# UKU100rs.net
KiCad netlist of a schematic drawn in Altium Designer
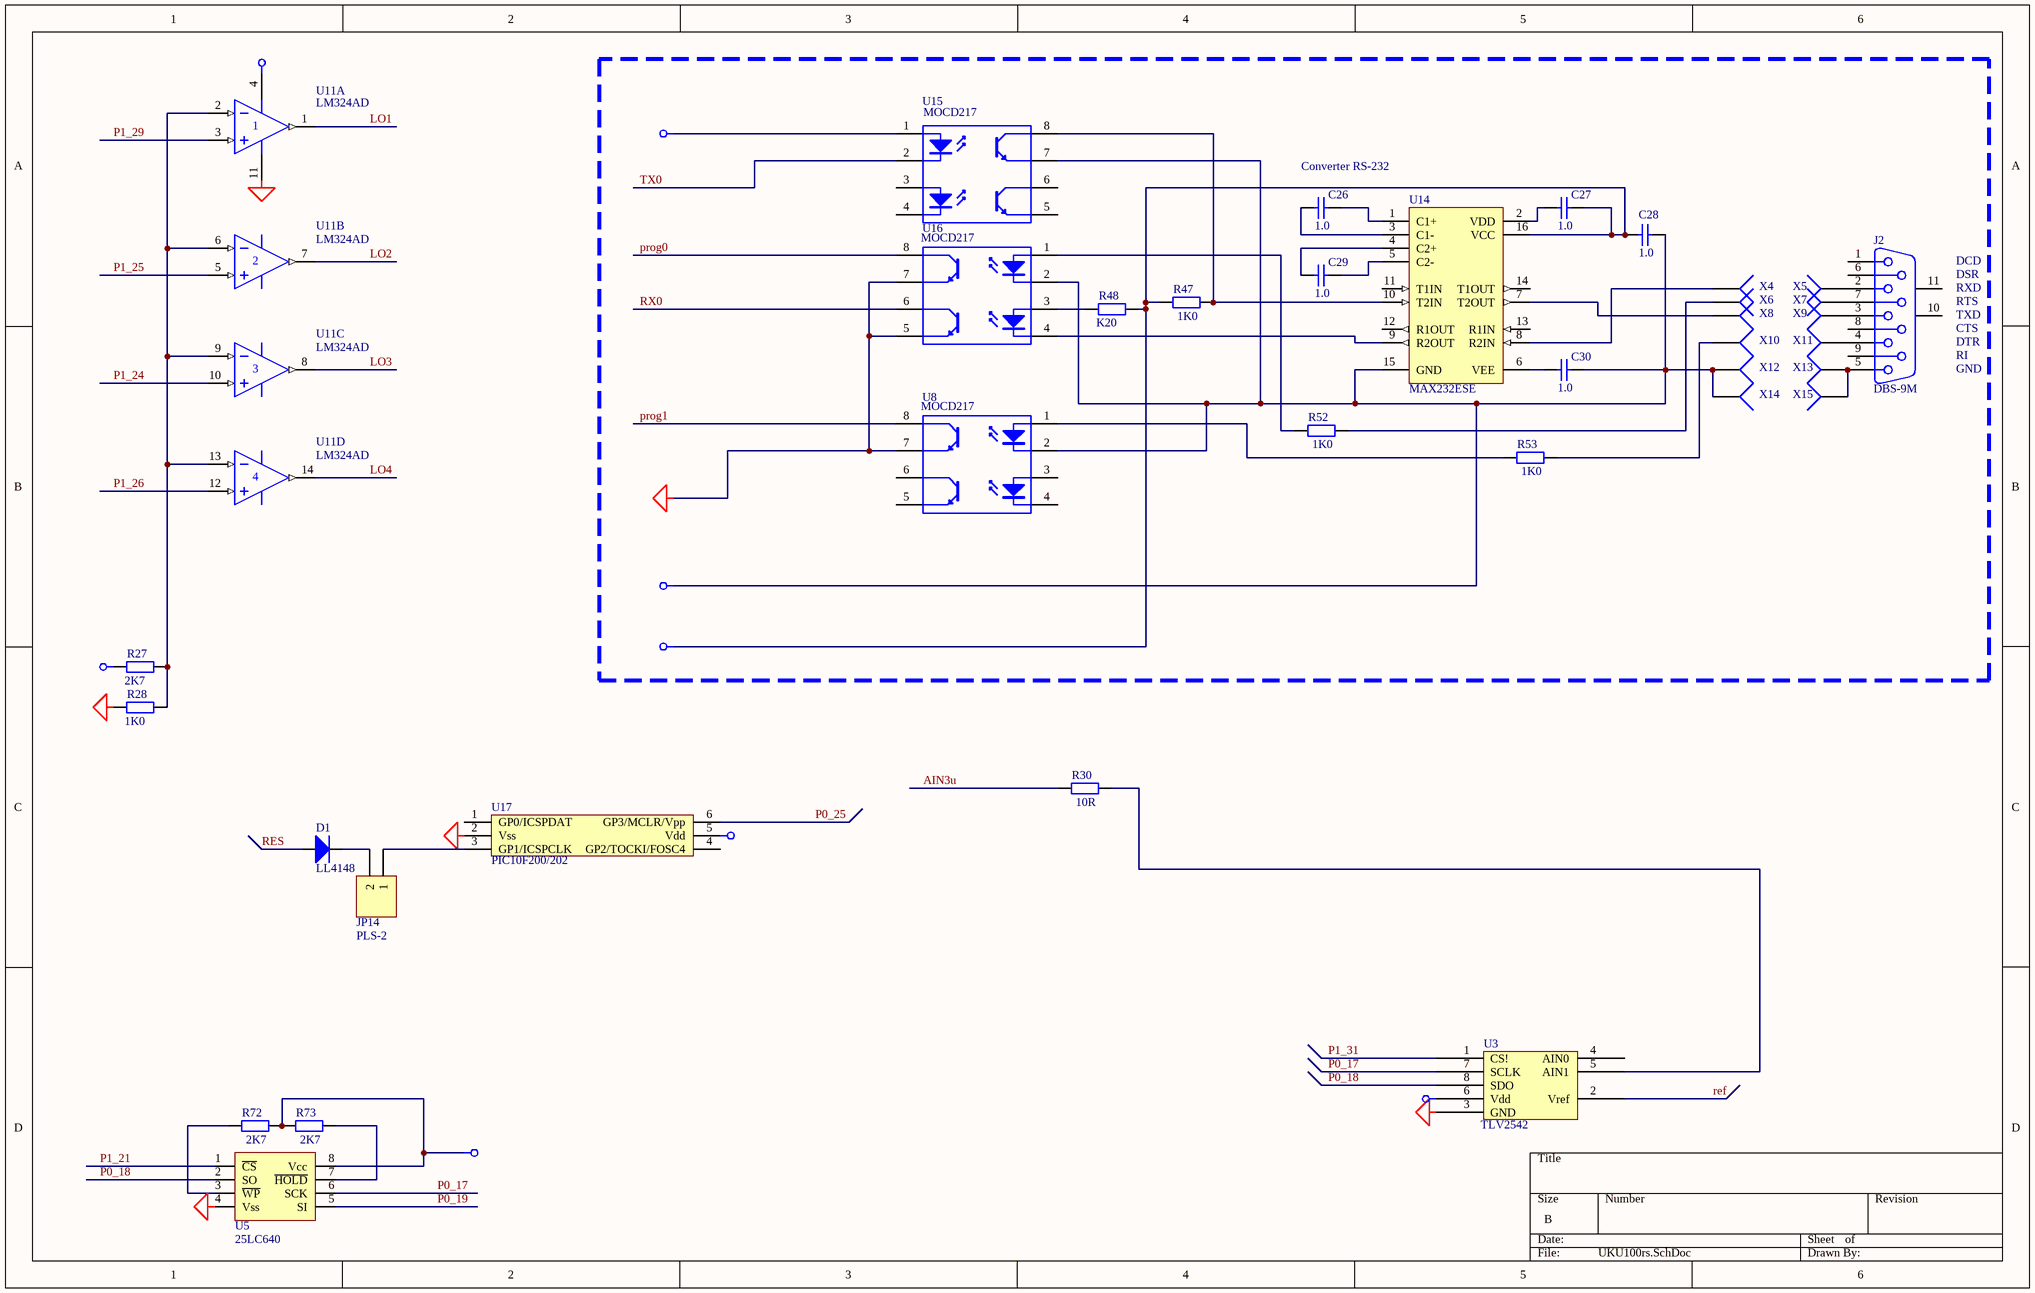
[diagram p0: UKU100rs.SchDoc]

(export (version "E")
  (design (tool "Eeschema 10.0.6"))
  (components
    (comp (ref "C26")
      (value "1.0")
      (footprint "C3216-1206")
      (description "Capacitor (Semiconductor SIM Model)")
      (fields (field (name "MANUFACTURER") "Generic Components") (field (name "PUBLISHER") "Altium Limited"))
      (libsource (lib "Miscellaneous Devices") (part "Cap Semi"))
    )
    (comp (ref "C27")
      (value "1.0")
      (footprint "_1206")
      (description "Capacitor (Semiconductor SIM Model)")
      (fields (field (name "MANUFACTURER") "Generic Components") (field (name "PUBLISHER") "Altium Limited"))
      (libsource (lib "Miscellaneous Devices") (part "Cap Semi"))
    )
    (comp (ref "C28")
      (value "1.0")
      (footprint "C3216-1206")
      (description "Capacitor (Semiconductor SIM Model)")
      (fields (field (name "MANUFACTURER") "Generic Components") (field (name "PUBLISHER") "Altium Limited"))
      (libsource (lib "Miscellaneous Devices") (part "Cap Semi"))
    )
    (comp (ref "C29")
      (value "1.0")
      (footprint "C3216-1206")
      (description "Capacitor (Semiconductor SIM Model)")
      (fields (field (name "MANUFACTURER") "Generic Components") (field (name "PUBLISHER") "Altium Limited"))
      (libsource (lib "Miscellaneous Devices") (part "Cap Semi"))
    )
    (comp (ref "C30")
      (value "1.0")
      (footprint "C3216-1206")
      (description "Capacitor (Semiconductor SIM Model)")
      (fields (field (name "MANUFACTURER") "Generic Components") (field (name "PUBLISHER") "Altium Limited"))
      (libsource (lib "Miscellaneous Devices") (part "Cap Semi"))
    )
    (comp (ref "D1")
      (value "LL4148")
      (footprint "_1206D")
      (description "Default Diode")
      (fields (field (name "MANUFACTURER") "Generic Components") (field (name "PUBLISHER") "Altium Limited"))
      (libsource (lib "Pal") (part "Diode"))
    )
    (comp (ref "J2")
      (value "DBS-9M")
      (footprint "DSUB_N9")
      (description "Receptacle Assembly, 9 Position, Right Angle")
      (fields (field (name "MANUFACTURER") "Generic Components") (field (name "PUBLISHER") "Altium Limited"))
      (libsource (lib "Miscellaneous Connectors") (part "D Connector 9"))
    )
    (comp (ref "JP14")
      (value "PLS-2")
      (footprint "HDR1X2")
      (description "Header, 2-Pin")
      (fields (field (name "MANUFACTURER") "Generic Components") (field (name "PUBLISHER") "Altium Limited"))
      (libsource (lib "Miscellaneous Connectors") (part "Header 2"))
    )
    (comp (ref "R27")
      (value "2K7")
      (footprint "_1206")
      (description "Resistor")
      (fields (field (name "MANUFACTURER") "Generic Components") (field (name "PUBLISHER") "Altium Limited"))
      (libsource (lib "Miscellaneous Devices") (part "Res2"))
    )
    (comp (ref "R28")
      (value "1K0")
      (footprint "_1206")
      (description "Resistor")
      (fields (field (name "MANUFACTURER") "Generic Components") (field (name "PUBLISHER") "Altium Limited"))
      (libsource (lib "Miscellaneous Devices") (part "Res2"))
    )
    (comp (ref "R30")
      (value "10R")
      (footprint "_1206")
      (description "Resistor")
      (fields (field (name "MANUFACTURER") "Generic Components") (field (name "PUBLISHER") "Altium Limited"))
      (libsource (lib "Miscellaneous Devices") (part "Res2"))
    )
    (comp (ref "R47")
      (value "1K0")
      (footprint "_1206")
      (description "Resistor")
      (fields (field (name "MANUFACTURER") "Generic Components") (field (name "PUBLISHER") "Altium Limited"))
      (libsource (lib "Miscellaneous Devices") (part "Res2"))
    )
    (comp (ref "R48")
      (value "K20")
      (footprint "_1206")
      (description "Resistor")
      (fields (field (name "MANUFACTURER") "Generic Components") (field (name "PUBLISHER") "Altium Limited"))
      (libsource (lib "Miscellaneous Devices") (part "Res2"))
    )
    (comp (ref "R52")
      (value "1K0")
      (footprint "_1206")
      (description "Resistor")
      (fields (field (name "MANUFACTURER") "Generic Components") (field (name "PUBLISHER") "Altium Limited"))
      (libsource (lib "Miscellaneous Devices") (part "Res2"))
    )
    (comp (ref "R53")
      (value "1K0")
      (footprint "_1206")
      (description "Resistor")
      (fields (field (name "MANUFACTURER") "Generic Components") (field (name "PUBLISHER") "Altium Limited"))
      (libsource (lib "Miscellaneous Devices") (part "Res2"))
    )
    (comp (ref "R72")
      (value "2K7")
      (footprint "_1206")
      (description "Resistor")
      (fields (field (name "MANUFACTURER") "Generic Components") (field (name "PUBLISHER") "Altium Limited"))
      (libsource (lib "Miscellaneous Devices") (part "Res2"))
    )
    (comp (ref "R73")
      (value "2K7")
      (footprint "_1206")
      (description "Resistor")
      (fields (field (name "MANUFACTURER") "Generic Components") (field (name "PUBLISHER") "Altium Limited"))
      (libsource (lib "Miscellaneous Devices") (part "Res2"))
    )
    (comp (ref "U3") (value "TLV2542") (footprint "SO-G8") (libsource (lib "MNS_A") (part "TLV2542")))
    (comp (ref "U5") (value "25LC640") (footprint "SO-G8/D5") (libsource (lib "PAL") (part "25LC640")))
    (comp (ref "U8") (value "MOCD217") (footprint "SO-G8") (libsource (lib "PAL") (part "MOCD217")))
    (comp (ref "U11")
      (value "LM324AD")
      (footprint "SO-G14/G3.3")
      (description "Quadruple Operational Amplifier")
      (fields (field (name "MANUFACTURER") "Texas Instruments") (field (name "PUBLISHER") "Altium Limited"))
      (libsource (lib "TI Operational Amplifier") (part "LM324AD"))
    )
    (comp (ref "U14")
      (value "MAX232ESE")
      (footprint "SO-G16")
      (description "+5V Powered, Multi-Channel RS-232 Driver/Receiver")
      (fields (field (name "MANUFACTURER") "Maxim") (field (name "PUBLISHER") "Altium Limited"))
      (libsource (lib "Maxim Communication Transceiver") (part "MAX232ESE"))
    )
    (comp (ref "U15") (value "MOCD217") (footprint "SO-G8") (libsource (lib "PAL") (part "MOCD217")))
    (comp (ref "U16") (value "MOCD217") (footprint "SO-G8") (libsource (lib "PAL") (part "MOCD217")))
    (comp (ref "U17")
      (value "PIC10F200/202")
      (footprint "SOT23 - 6")
      (libsource (lib "PAL") (part "PIC10F200/202"))
    )
    (comp (ref "X4")
      (value "~")
      (footprint "PIN1")
      (description "Socket")
      (fields (field (name "MANUFACTURER") "Generic Components") (field (name "PUBLISHER") "Altium Limited"))
      (libsource (lib "Miscellaneous Connectors") (part "Socket"))
    )
    (comp (ref "X5")
      (value "~")
      (footprint "PIN1")
      (description "Socket")
      (fields (field (name "MANUFACTURER") "Generic Components") (field (name "PUBLISHER") "Altium Limited"))
      (libsource (lib "Miscellaneous Connectors") (part "Socket"))
    )
    (comp (ref "X6")
      (value "~")
      (footprint "PIN1")
      (description "Socket")
      (fields (field (name "MANUFACTURER") "Generic Components") (field (name "PUBLISHER") "Altium Limited"))
      (libsource (lib "Miscellaneous Connectors") (part "Socket"))
    )
    (comp (ref "X7")
      (value "~")
      (footprint "PIN1")
      (description "Socket")
      (fields (field (name "MANUFACTURER") "Generic Components") (field (name "PUBLISHER") "Altium Limited"))
      (libsource (lib "Miscellaneous Connectors") (part "Socket"))
    )
    (comp (ref "X8")
      (value "~")
      (footprint "PIN1")
      (description "Socket")
      (fields (field (name "MANUFACTURER") "Generic Components") (field (name "PUBLISHER") "Altium Limited"))
      (libsource (lib "Miscellaneous Connectors") (part "Socket"))
    )
    (comp (ref "X9")
      (value "~")
      (footprint "PIN1")
      (description "Socket")
      (fields (field (name "MANUFACTURER") "Generic Components") (field (name "PUBLISHER") "Altium Limited"))
      (libsource (lib "Miscellaneous Connectors") (part "Socket"))
    )
    (comp (ref "X10")
      (value "~")
      (footprint "PIN1")
      (description "Socket")
      (fields (field (name "MANUFACTURER") "Generic Components") (field (name "PUBLISHER") "Altium Limited"))
      (libsource (lib "Miscellaneous Connectors") (part "Socket"))
    )
    (comp (ref "X11")
      (value "~")
      (footprint "PIN1")
      (description "Socket")
      (fields (field (name "MANUFACTURER") "Generic Components") (field (name "PUBLISHER") "Altium Limited"))
      (libsource (lib "Miscellaneous Connectors") (part "Socket"))
    )
    (comp (ref "X12")
      (value "~")
      (footprint "PIN1")
      (description "Socket")
      (fields (field (name "MANUFACTURER") "Generic Components") (field (name "PUBLISHER") "Altium Limited"))
      (libsource (lib "Miscellaneous Connectors") (part "Socket"))
    )
    (comp (ref "X13")
      (value "~")
      (footprint "PIN1")
      (description "Socket")
      (fields (field (name "MANUFACTURER") "Generic Components") (field (name "PUBLISHER") "Altium Limited"))
      (libsource (lib "Miscellaneous Connectors") (part "Socket"))
    )
    (comp (ref "X14")
      (value "~")
      (footprint "PIN1")
      (description "Socket")
      (fields (field (name "MANUFACTURER") "Generic Components") (field (name "PUBLISHER") "Altium Limited"))
      (libsource (lib "Miscellaneous Connectors") (part "Socket"))
    )
    (comp (ref "X15")
      (value "~")
      (footprint "PIN1")
      (description "Socket")
      (fields (field (name "MANUFACTURER") "Generic Components") (field (name "PUBLISHER") "Altium Limited"))
      (libsource (lib "Miscellaneous Connectors") (part "Socket"))
    )
  )
  (nets
    (net (code "1") (name "+3v3") (class "Default")
      (node (ref "U17") (pin "5") (pinfunction "Vdd_5") (pintype "passive"))
    )
    (net (code "2") (name "+3v3_") (class "Default")
      (node (ref "U15") (pin "1") (pinfunction "A_1") (pintype "passive"))
    )
    (net (code "3") (name "+5v") (class "Default")
      (node (ref "R27") (pin "1") (pinfunction "1_1") (pintype "passive"))
      (node (ref "R72") (pin "2") (pinfunction "2_2") (pintype "passive"))
      (node (ref "R73") (pin "1") (pinfunction "1_1") (pintype "passive"))
      (node (ref "U11") (pin "4") (pinfunction "V+_4") (pintype "power_in"))
      (node (ref "U3") (pin "6") (pinfunction "Vdd_6") (pintype "passive"))
      (node (ref "U5") (pin "8") (pinfunction "Vcc_8") (pintype "passive"))
    )
    (net (code "4") (name "+5v_iz") (class "Default")
      (node (ref "C27") (pin "2") (pinfunction "2_2") (pintype "passive"))
      (node (ref "C28") (pin "1") (pinfunction "1_1") (pintype "passive"))
      (node (ref "R47") (pin "1") (pinfunction "1_1") (pintype "passive"))
      (node (ref "R48") (pin "2") (pinfunction "2_2") (pintype "passive"))
      (node (ref "U14") (pin "16") (pinfunction "VCC_16") (pintype "power_in"))
    )
    (net (code "5") (name "-5v_iz") (class "Default")
      (node (ref "C28") (pin "2") (pinfunction "2_2") (pintype "passive"))
      (node (ref "C30") (pin "2") (pinfunction "2_2") (pintype "passive"))
      (node (ref "U14") (pin "15") (pinfunction "GND_15") (pintype "power_in"))
      (node (ref "U15") (pin "7") (pinfunction "E_7") (pintype "passive"))
      (node (ref "U16") (pin "2") (pinfunction "K_2") (pintype "passive"))
      (node (ref "U8") (pin "2") (pinfunction "K_2") (pintype "passive"))
      (node (ref "X12") (pin "1") (pinfunction "1_1") (pintype "passive"))
      (node (ref "X14") (pin "1") (pinfunction "1_1") (pintype "passive"))
    )
    (net (code "6") (name "/AIN3u") (class "Default")
      (node (ref "R30") (pin "1") (pinfunction "1_1") (pintype "passive"))
    )
    (net (code "7") (name "/LO1") (class "Default")
      (node (ref "U11") (pin "1") (pinfunction "OUT_1") (pintype "output"))
    )
    (net (code "8") (name "/LO2") (class "Default")
      (node (ref "U11") (pin "7") (pinfunction "OUT_7") (pintype "output"))
    )
    (net (code "9") (name "/LO3") (class "Default")
      (node (ref "U11") (pin "8") (pinfunction "OUT_8") (pintype "output"))
    )
    (net (code "10") (name "/LO4") (class "Default")
      (node (ref "U11") (pin "14") (pinfunction "OUT_14") (pintype "output"))
    )
    (net (code "11") (name "/P0_17") (class "Default")
      (node (ref "U3") (pin "7") (pinfunction "SCLK_7") (pintype "passive"))
      (node (ref "U5") (pin "6") (pinfunction "SCK_6") (pintype "passive"))
    )
    (net (code "12") (name "/P0_18") (class "Default")
      (node (ref "U3") (pin "8") (pinfunction "SDO_8") (pintype "passive"))
      (node (ref "U5") (pin "2") (pinfunction "SO_2") (pintype "passive"))
    )
    (net (code "13") (name "/P0_19") (class "Default")
      (node (ref "U5") (pin "5") (pinfunction "SI_5") (pintype "passive"))
    )
    (net (code "14") (name "/P0_25") (class "Default")
      (node (ref "U17") (pin "6") (pinfunction "GP3/MCLR/Vpp_6") (pintype "passive"))
    )
    (net (code "15") (name "/P1_21") (class "Default")
      (node (ref "U5") (pin "1") (pinfunction "~{CS}_1") (pintype "passive"))
    )
    (net (code "16") (name "/P1_24") (class "Default")
      (node (ref "U11") (pin "10") (pinfunction "IN+_10") (pintype "input"))
    )
    (net (code "17") (name "/P1_25") (class "Default")
      (node (ref "U11") (pin "5") (pinfunction "IN+_5") (pintype "input"))
    )
    (net (code "18") (name "/P1_26") (class "Default")
      (node (ref "U11") (pin "12") (pinfunction "IN+_12") (pintype "input"))
    )
    (net (code "19") (name "/P1_29") (class "Default")
      (node (ref "U11") (pin "3") (pinfunction "IN+_3") (pintype "input"))
    )
    (net (code "20") (name "/P1_31") (class "Default")
      (node (ref "U3") (pin "1") (pinfunction "CS!_1") (pintype "passive"))
    )
    (net (code "21") (name "/RES") (class "Default")
      (node (ref "D1") (pin "1") (pinfunction "A_1") (pintype "passive"))
    )
    (net (code "22") (name "/RX0") (class "Default")
      (node (ref "U16") (pin "6") (pinfunction "C_6") (pintype "passive"))
    )
    (net (code "23") (name "/TX0") (class "Default")
      (node (ref "U15") (pin "2") (pinfunction "K_2") (pintype "passive"))
    )
    (net (code "24") (name "/prog0") (class "Default")
      (node (ref "U16") (pin "8") (pinfunction "C_8") (pintype "passive"))
    )
    (net (code "25") (name "/prog1") (class "Default")
      (node (ref "U8") (pin "8") (pinfunction "C_8") (pintype "passive"))
    )
    (net (code "26") (name "/ref") (class "Default")
      (node (ref "U3") (pin "2") (pinfunction "Vref_2") (pintype "passive"))
    )
    (net (code "27") (name "GND") (class "Default")
      (node (ref "R28") (pin "1") (pinfunction "1_1") (pintype "passive"))
      (node (ref "U11") (pin "11") (pinfunction "V-_11") (pintype "power_in"))
      (node (ref "U16") (pin "5") (pinfunction "E_5") (pintype "passive"))
      (node (ref "U16") (pin "7") (pinfunction "E_7") (pintype "passive"))
      (node (ref "U17") (pin "2") (pinfunction "Vss_2") (pintype "passive"))
      (node (ref "U3") (pin "3") (pinfunction "GND_3") (pintype "passive"))
      (node (ref "U5") (pin "4") (pinfunction "Vss_4") (pintype "passive"))
      (node (ref "U8") (pin "7") (pinfunction "E_7") (pintype "passive"))
    )
    (net (code "28") (name "Net-(D1-K)") (class "Default")
      (node (ref "D1") (pin "2") (pinfunction "K_2") (pintype "passive"))
      (node (ref "JP14") (pin "2") (pinfunction "2_2") (pintype "passive"))
    )
    (net (code "29") (name "Net-(J2-Pad2)") (class "Default")
      (node (ref "J2") (pin "2") (pinfunction "2_2") (pintype "passive"))
      (node (ref "X5") (pin "1") (pinfunction "1_1") (pintype "passive"))
    )
    (net (code "30") (name "Net-(J2-Pad3)") (class "Default")
      (node (ref "J2") (pin "3") (pinfunction "3_3") (pintype "passive"))
      (node (ref "X9") (pin "1") (pinfunction "1_1") (pintype "passive"))
    )
    (net (code "31") (name "Net-(J2-Pad4)") (class "Default")
      (node (ref "J2") (pin "4") (pinfunction "4_4") (pintype "passive"))
      (node (ref "X11") (pin "1") (pinfunction "1_1") (pintype "passive"))
    )
    (net (code "32") (name "Net-(J2-Pad5)") (class "Default")
      (node (ref "J2") (pin "5") (pinfunction "5_5") (pintype "passive"))
      (node (ref "X13") (pin "1") (pinfunction "1_1") (pintype "passive"))
      (node (ref "X15") (pin "1") (pinfunction "1_1") (pintype "passive"))
    )
    (net (code "33") (name "Net-(J2-Pad7)") (class "Default")
      (node (ref "J2") (pin "7") (pinfunction "7_7") (pintype "passive"))
      (node (ref "X7") (pin "1") (pinfunction "1_1") (pintype "passive"))
    )
    (net (code "34") (name "Net-(R48-Pad1)") (class "Default")
      (node (ref "R48") (pin "1") (pinfunction "1_1") (pintype "passive"))
      (node (ref "U16") (pin "3") (pinfunction "A_3") (pintype "passive"))
    )
    (net (code "35") (name "Net-(R52-Pad1)") (class "Default")
      (node (ref "R52") (pin "1") (pinfunction "1_1") (pintype "passive"))
      (node (ref "U16") (pin "1") (pinfunction "A_1") (pintype "passive"))
    )
    (net (code "36") (name "Net-(R52-Pad2)") (class "Default")
      (node (ref "R52") (pin "2") (pinfunction "2_2") (pintype "passive"))
      (node (ref "X6") (pin "1") (pinfunction "1_1") (pintype "passive"))
    )
    (net (code "37") (name "Net-(R53-Pad1)") (class "Default")
      (node (ref "R53") (pin "1") (pinfunction "1_1") (pintype "passive"))
      (node (ref "U8") (pin "1") (pinfunction "A_1") (pintype "passive"))
    )
    (net (code "38") (name "Net-(R53-Pad2)") (class "Default")
      (node (ref "R53") (pin "2") (pinfunction "2_2") (pintype "passive"))
      (node (ref "X10") (pin "1") (pinfunction "1_1") (pintype "passive"))
    )
    (net (code "39") (name "Net-(U3-AIN1)") (class "Default")
      (node (ref "R30") (pin "2") (pinfunction "2_2") (pintype "passive"))
      (node (ref "U3") (pin "5") (pinfunction "AIN1_5") (pintype "passive"))
    )
    (net (code "40") (name "Net-(U5-~{HOLD})") (class "Default")
      (node (ref "R73") (pin "2") (pinfunction "2_2") (pintype "passive"))
      (node (ref "U5") (pin "7") (pinfunction "~{HOLD}_7") (pintype "passive"))
    )
    (net (code "41") (name "Net-(U5-~{WP})") (class "Default")
      (node (ref "R72") (pin "1") (pinfunction "1_1") (pintype "passive"))
      (node (ref "U5") (pin "3") (pinfunction "~{WP}_3") (pintype "passive"))
    )
    (net (code "42") (name "Net-(U11A-IN-)") (class "Default")
      (node (ref "R27") (pin "2") (pinfunction "2_2") (pintype "passive"))
      (node (ref "R28") (pin "2") (pinfunction "2_2") (pintype "passive"))
      (node (ref "U11") (pin "13") (pinfunction "IN-_13") (pintype "input"))
      (node (ref "U11") (pin "2") (pinfunction "IN-_2") (pintype "input"))
      (node (ref "U11") (pin "6") (pinfunction "IN-_6") (pintype "input"))
      (node (ref "U11") (pin "9") (pinfunction "IN-_9") (pintype "input"))
    )
    (net (code "43") (name "Net-(U14-C1+)") (class "Default")
      (node (ref "C26") (pin "2") (pinfunction "2_2") (pintype "passive"))
      (node (ref "U14") (pin "1") (pinfunction "C1+_1") (pintype "passive"))
    )
    (net (code "44") (name "Net-(U14-C1-)") (class "Default")
      (node (ref "C26") (pin "1") (pinfunction "1_1") (pintype "passive"))
      (node (ref "U14") (pin "3") (pinfunction "C1-_3") (pintype "passive"))
    )
    (net (code "45") (name "Net-(U14-C2+)") (class "Default")
      (node (ref "C29") (pin "1") (pinfunction "1_1") (pintype "passive"))
      (node (ref "U14") (pin "4") (pinfunction "C2+_4") (pintype "passive"))
    )
    (net (code "46") (name "Net-(U14-C2-)") (class "Default")
      (node (ref "C29") (pin "2") (pinfunction "2_2") (pintype "passive"))
      (node (ref "U14") (pin "5") (pinfunction "C2-_5") (pintype "passive"))
    )
    (net (code "47") (name "Net-(U14-R2IN)") (class "Default")
      (node (ref "U14") (pin "8") (pinfunction "R2IN_8") (pintype "input"))
      (node (ref "X4") (pin "1") (pinfunction "1_1") (pintype "passive"))
    )
    (net (code "48") (name "Net-(U14-R2OUT)") (class "Default")
      (node (ref "U14") (pin "9") (pinfunction "R2OUT_9") (pintype "output"))
      (node (ref "U16") (pin "4") (pinfunction "K_4") (pintype "passive"))
    )
    (net (code "49") (name "Net-(U14-T2IN)") (class "Default")
      (node (ref "R47") (pin "2") (pinfunction "2_2") (pintype "passive"))
      (node (ref "U14") (pin "10") (pinfunction "T2IN_10") (pintype "input"))
      (node (ref "U15") (pin "8") (pinfunction "C_8") (pintype "passive"))
    )
    (net (code "50") (name "Net-(U14-T2OUT)") (class "Default")
      (node (ref "U14") (pin "7") (pinfunction "T2OUT_7") (pintype "output"))
      (node (ref "X8") (pin "1") (pinfunction "1_1") (pintype "passive"))
    )
    (net (code "51") (name "Net-(U14-VDD)") (class "Default")
      (node (ref "C27") (pin "1") (pinfunction "1_1") (pintype "passive"))
      (node (ref "U14") (pin "2") (pinfunction "VDD_2") (pintype "power_in"))
    )
    (net (code "52") (name "Net-(U14-VEE)") (class "Default")
      (node (ref "C30") (pin "1") (pinfunction "1_1") (pintype "passive"))
      (node (ref "U14") (pin "6") (pinfunction "VEE_6") (pintype "power_in"))
    )
    (net (code "53") (name "Net-(U17-GP1{slash}ICSPCLK)") (class "Default")
      (node (ref "JP14") (pin "1") (pinfunction "1_1") (pintype "passive"))
      (node (ref "U17") (pin "3") (pinfunction "GP1/ICSPCLK_3") (pintype "passive"))
    )
    (net (code "54") (name "unconnected-(J2-MH1-Pad10)") (class "Default")
      (node (ref "J2") (pin "10") (pinfunction "MH1_10") (pintype "passive"))
    )
    (net (code "55") (name "unconnected-(J2-MH2-Pad11)") (class "Default")
      (node (ref "J2") (pin "11") (pinfunction "MH2_11") (pintype "passive"))
    )
    (net (code "56") (name "unconnected-(J2-Pad1)") (class "Default")
      (node (ref "J2") (pin "1") (pinfunction "1_1") (pintype "passive"))
    )
    (net (code "57") (name "unconnected-(J2-Pad6)") (class "Default")
      (node (ref "J2") (pin "6") (pinfunction "6_6") (pintype "passive"))
    )
    (net (code "58") (name "unconnected-(J2-Pad8)") (class "Default")
      (node (ref "J2") (pin "8") (pinfunction "8_8") (pintype "passive"))
    )
    (net (code "59") (name "unconnected-(J2-Pad9)") (class "Default")
      (node (ref "J2") (pin "9") (pinfunction "9_9") (pintype "passive"))
    )
    (net (code "60") (name "unconnected-(U3-AIN0-Pad4)") (class "Default")
      (node (ref "U3") (pin "4") (pinfunction "AIN0_4") (pintype "passive"))
    )
    (net (code "61") (name "unconnected-(U8-A-Pad3)") (class "Default")
      (node (ref "U8") (pin "3") (pinfunction "A_3") (pintype "passive"))
    )
    (net (code "62") (name "unconnected-(U8-C-Pad6)") (class "Default")
      (node (ref "U8") (pin "6") (pinfunction "C_6") (pintype "passive"))
    )
    (net (code "63") (name "unconnected-(U8-E-Pad5)") (class "Default")
      (node (ref "U8") (pin "5") (pinfunction "E_5") (pintype "passive"))
    )
    (net (code "64") (name "unconnected-(U8-K-Pad4)") (class "Default")
      (node (ref "U8") (pin "4") (pinfunction "K_4") (pintype "passive"))
    )
    (net (code "65") (name "unconnected-(U14-R1IN-Pad13)") (class "Default")
      (node (ref "U14") (pin "13") (pinfunction "R1IN_13") (pintype "input"))
    )
    (net (code "66") (name "unconnected-(U14-R1OUT-Pad12)") (class "Default")
      (node (ref "U14") (pin "12") (pinfunction "R1OUT_12") (pintype "output"))
    )
    (net (code "67") (name "unconnected-(U14-T1IN-Pad11)") (class "Default")
      (node (ref "U14") (pin "11") (pinfunction "T1IN_11") (pintype "input"))
    )
    (net (code "68") (name "unconnected-(U14-T1OUT-Pad14)") (class "Default")
      (node (ref "U14") (pin "14") (pinfunction "T1OUT_14") (pintype "output"))
    )
    (net (code "69") (name "unconnected-(U15-A-Pad3)") (class "Default")
      (node (ref "U15") (pin "3") (pinfunction "A_3") (pintype "passive"))
    )
    (net (code "70") (name "unconnected-(U15-C-Pad6)") (class "Default")
      (node (ref "U15") (pin "6") (pinfunction "C_6") (pintype "passive"))
    )
    (net (code "71") (name "unconnected-(U15-E-Pad5)") (class "Default")
      (node (ref "U15") (pin "5") (pinfunction "E_5") (pintype "passive"))
    )
    (net (code "72") (name "unconnected-(U15-K-Pad4)") (class "Default")
      (node (ref "U15") (pin "4") (pinfunction "K_4") (pintype "passive"))
    )
    (net (code "73") (name "unconnected-(U17-GP0{slash}ICSPDAT-Pad1)") (class "Default")
      (node (ref "U17") (pin "1") (pinfunction "GP0/ICSPDAT_1") (pintype "passive"))
    )
    (net (code "74") (name "unconnected-(U17-GP2{slash}TOCKI{slash}FOSC4-Pad4)") (class "Default")
      (node (ref "U17") (pin "4") (pinfunction "GP2/TOCKI/FOSC4_4") (pintype "passive"))
    )
  )
)
